# ttgo-diy.net
KiCad netlist of a schematic drawn in EAGLE
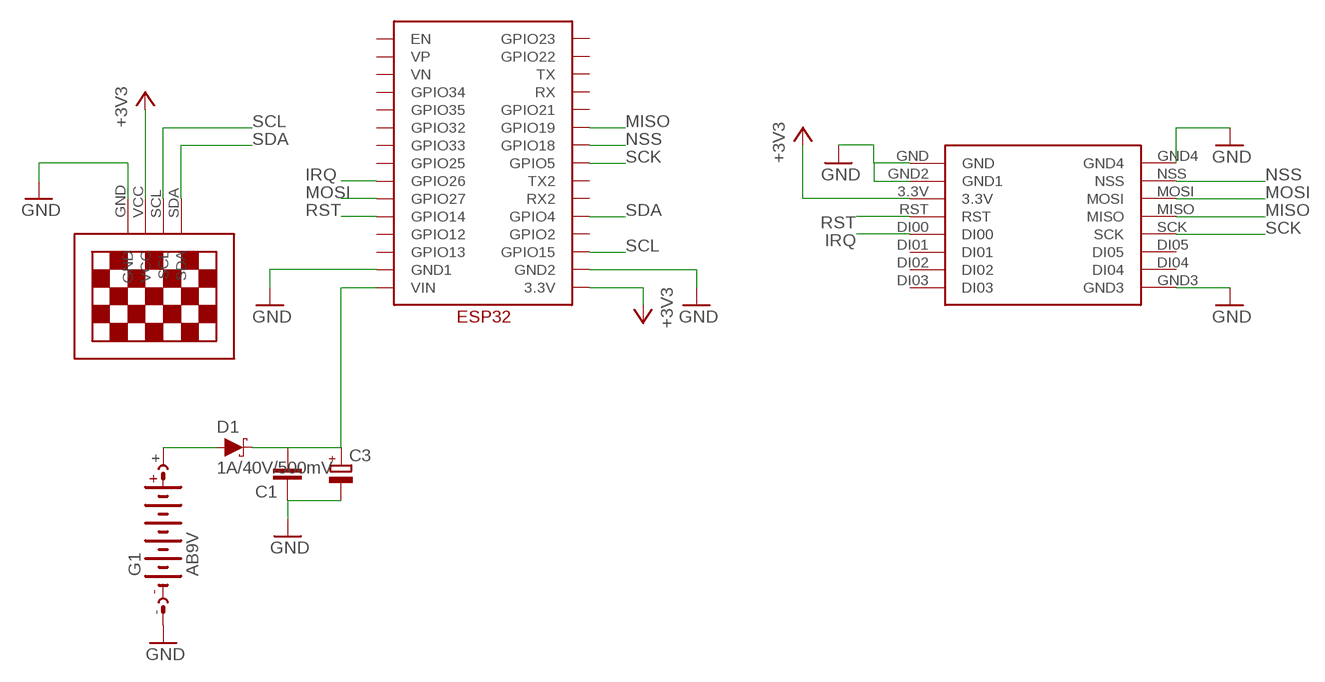
[diagram p0: schematic, sheet 1]

(export (version "E")
  (design (tool "Eeschema 10.0.6"))
  (components
    (comp (ref "C1")
      (value "C-EUC1206")
      (footprint "eagle-import:C1206")
      (libsource (lib "eagle-import") (part "C-EUC1206"))
    )
    (comp (ref "C3")
      (value "CPOL-EUCT6032")
      (footprint "eagle-import:CT6032")
      (libsource (lib "eagle-import") (part "CPOL-EUCT6032"))
    )
    (comp (ref "D1")
      (value "1A/40V/500mV")
      (footprint "eagle-import:SMA-DIODE")
      (libsource (lib "eagle-import") (part "DIODE-SCHOTTKY-SS14"))
    )
    (comp (ref "G1")
      (value "AB9V")
      (footprint "eagle-import:AB9V")
      (libsource (lib "eagle-import") (part "AB9V"))
    )
    (comp (ref "U$1")
      (value "LORA-02DIL")
      (footprint "eagle-import:DIL8X11")
      (libsource (lib "eagle-import") (part "LORA-02DIL"))
    )
    (comp (ref "U$2")
      (value "ESP32")
      (footprint "eagle-import:ESP32")
      (libsource (lib "eagle-import") (part "ESP32"))
    )
    (comp (ref "U$3")
      (value "13\"OLED13\"OLED")
      (footprint "eagle-import:1.3_OLED")
      (libsource (lib "eagle-import") (part "13{dblquote}OLED13{dblquote}OLED"))
    )
  )
  (nets
    (net (code "1") (name "+3V3") (class "Default")
      (node (ref "U$1") (pin "3.3V") (pinfunction "3.3V_3.3V") (pintype "power_in"))
      (node (ref "U$2") (pin "3.3V") (pinfunction "3.3V_3.3V") (pintype "bidirectional"))
      (node (ref "U$3") (pin "VCC") (pinfunction "VCC_VCC") (pintype "bidirectional"))
    )
    (net (code "2") (name "/IRQ") (class "Default")
      (node (ref "U$1") (pin "DI00") (pinfunction "DI00_DI00") (pintype "bidirectional"))
      (node (ref "U$2") (pin "GPIO26") (pinfunction "GPIO26_GPIO26") (pintype "bidirectional"))
    )
    (net (code "3") (name "/MISO") (class "Default")
      (node (ref "U$1") (pin "MISO") (pinfunction "MISO_MISO") (pintype "input"))
      (node (ref "U$2") (pin "GPIO19") (pinfunction "GPIO19_GPIO19") (pintype "bidirectional"))
    )
    (net (code "4") (name "/MOSI") (class "Default")
      (node (ref "U$1") (pin "MOSI") (pinfunction "MOSI_MOSI") (pintype "output"))
      (node (ref "U$2") (pin "GPIO27") (pinfunction "GPIO27_GPIO27") (pintype "bidirectional"))
    )
    (net (code "5") (name "/NSS") (class "Default")
      (node (ref "U$1") (pin "NSS") (pinfunction "NSS_NSS") (pintype "input"))
      (node (ref "U$2") (pin "GPIO18") (pinfunction "GPIO18_GPIO18") (pintype "bidirectional"))
    )
    (net (code "6") (name "/RST") (class "Default")
      (node (ref "U$1") (pin "RST") (pinfunction "RST_RST") (pintype "input"))
      (node (ref "U$2") (pin "GPIO14") (pinfunction "GPIO14_GPIO14") (pintype "bidirectional"))
    )
    (net (code "7") (name "/SCK") (class "Default")
      (node (ref "U$1") (pin "SCK") (pinfunction "SCK_SCK") (pintype "open_collector"))
      (node (ref "U$2") (pin "GPIO5") (pinfunction "GPIO5_GPIO5") (pintype "bidirectional"))
    )
    (net (code "8") (name "/SCL") (class "Default")
      (node (ref "U$2") (pin "GPIO15") (pinfunction "GPIO15_GPIO15") (pintype "bidirectional"))
      (node (ref "U$3") (pin "SCL") (pinfunction "SCL_SCL") (pintype "bidirectional"))
    )
    (net (code "9") (name "/SDA") (class "Default")
      (node (ref "U$2") (pin "GPIO4") (pinfunction "GPIO4_GPIO4") (pintype "bidirectional"))
      (node (ref "U$3") (pin "SDA") (pinfunction "SDA_SDA") (pintype "bidirectional"))
    )
    (net (code "10") (name "GND") (class "Default")
      (node (ref "C1") (pin "1") (pinfunction "1_1") (pintype "passive"))
      (node (ref "C3") (pin "-") (pinfunction "-_-") (pintype "passive"))
      (node (ref "G1") (pin "-") (pinfunction "-_-") (pintype "passive"))
      (node (ref "U$1") (pin "GND") (pinfunction "GND_GND") (pintype "power_in"))
      (node (ref "U$1") (pin "GND2") (pinfunction "GND1_GND2") (pintype "power_in"))
      (node (ref "U$1") (pin "GND3") (pinfunction "GND3_GND3") (pintype "power_in"))
      (node (ref "U$1") (pin "GND4") (pinfunction "GND4_GND4") (pintype "power_in"))
      (node (ref "U$2") (pin "GND1") (pinfunction "GND1_GND1") (pintype "bidirectional"))
      (node (ref "U$2") (pin "GND2") (pinfunction "GND2_GND2") (pintype "bidirectional"))
      (node (ref "U$3") (pin "GND") (pinfunction "GND_GND") (pintype "bidirectional"))
    )
    (net (code "11") (name "Net-(C1-Pad2)") (class "Default")
      (node (ref "C1") (pin "2") (pinfunction "2_2") (pintype "passive"))
      (node (ref "C3") (pin "+") (pinfunction "+_+") (pintype "passive"))
      (node (ref "D1") (pin "C") (pinfunction "C_C") (pintype "passive"))
      (node (ref "U$2") (pin "VIN") (pinfunction "VIN_VIN") (pintype "bidirectional"))
    )
    (net (code "12") (name "Net-(D1-PadA)") (class "Default")
      (node (ref "D1") (pin "A") (pinfunction "A_A") (pintype "passive"))
      (node (ref "G1") (pin "+") (pinfunction "+_+") (pintype "passive"))
    )
    (net (code "13") (name "unconnected-(U$1-PadDI01)") (class "Default")
      (node (ref "U$1") (pin "DI01") (pinfunction "DI01_DI01") (pintype "bidirectional"))
    )
    (net (code "14") (name "unconnected-(U$1-PadDI02)") (class "Default")
      (node (ref "U$1") (pin "DI02") (pinfunction "DI02_DI02") (pintype "bidirectional"))
    )
    (net (code "15") (name "unconnected-(U$1-PadDI03)") (class "Default")
      (node (ref "U$1") (pin "DI03") (pinfunction "DI03_DI03") (pintype "bidirectional"))
    )
    (net (code "16") (name "unconnected-(U$1-PadDI04)") (class "Default")
      (node (ref "U$1") (pin "DI04") (pinfunction "DI04_DI04") (pintype "bidirectional"))
    )
    (net (code "17") (name "unconnected-(U$1-PadDI05)") (class "Default")
      (node (ref "U$1") (pin "DI05") (pinfunction "DI05_DI05") (pintype "bidirectional"))
    )
    (net (code "18") (name "unconnected-(U$2-PadEN)") (class "Default")
      (node (ref "U$2") (pin "EN") (pinfunction "EN_EN") (pintype "bidirectional"))
    )
    (net (code "19") (name "unconnected-(U$2-PadGPIO2)") (class "Default")
      (node (ref "U$2") (pin "GPIO2") (pinfunction "GPIO2_GPIO2") (pintype "bidirectional"))
    )
    (net (code "20") (name "unconnected-(U$2-PadGPIO12)") (class "Default")
      (node (ref "U$2") (pin "GPIO12") (pinfunction "GPIO12_GPIO12") (pintype "bidirectional"))
    )
    (net (code "21") (name "unconnected-(U$2-PadGPIO13)") (class "Default")
      (node (ref "U$2") (pin "GPIO13") (pinfunction "GPIO13_GPIO13") (pintype "bidirectional"))
    )
    (net (code "22") (name "unconnected-(U$2-PadGPIO21)") (class "Default")
      (node (ref "U$2") (pin "GPIO21") (pinfunction "GPIO21_GPIO21") (pintype "bidirectional"))
    )
    (net (code "23") (name "unconnected-(U$2-PadGPIO22)") (class "Default")
      (node (ref "U$2") (pin "GPIO22") (pinfunction "GPIO22_GPIO22") (pintype "bidirectional"))
    )
    (net (code "24") (name "unconnected-(U$2-PadGPIO23)") (class "Default")
      (node (ref "U$2") (pin "GPIO23") (pinfunction "GPIO23_GPIO23") (pintype "bidirectional"))
    )
    (net (code "25") (name "unconnected-(U$2-PadGPIO25)") (class "Default")
      (node (ref "U$2") (pin "GPIO25") (pinfunction "GPIO25_GPIO25") (pintype "bidirectional"))
    )
    (net (code "26") (name "unconnected-(U$2-PadGPIO32)") (class "Default")
      (node (ref "U$2") (pin "GPIO32") (pinfunction "GPIO32_GPIO32") (pintype "bidirectional"))
    )
    (net (code "27") (name "unconnected-(U$2-PadGPIO33)") (class "Default")
      (node (ref "U$2") (pin "GPIO33") (pinfunction "GPIO33_GPIO33") (pintype "bidirectional"))
    )
    (net (code "28") (name "unconnected-(U$2-PadGPIO34)") (class "Default")
      (node (ref "U$2") (pin "GPIO34") (pinfunction "GPIO34_GPIO34") (pintype "bidirectional"))
    )
    (net (code "29") (name "unconnected-(U$2-PadGPIO35)") (class "Default")
      (node (ref "U$2") (pin "GPIO35") (pinfunction "GPIO35_GPIO35") (pintype "bidirectional"))
    )
    (net (code "30") (name "unconnected-(U$2-PadRX)") (class "Default")
      (node (ref "U$2") (pin "RX") (pinfunction "RX_RX") (pintype "bidirectional"))
    )
    (net (code "31") (name "unconnected-(U$2-PadRX2)") (class "Default")
      (node (ref "U$2") (pin "RX2") (pinfunction "RX2_RX2") (pintype "bidirectional"))
    )
    (net (code "32") (name "unconnected-(U$2-PadTX)") (class "Default")
      (node (ref "U$2") (pin "TX") (pinfunction "TX_TX") (pintype "bidirectional"))
    )
    (net (code "33") (name "unconnected-(U$2-PadTX2)") (class "Default")
      (node (ref "U$2") (pin "TX2") (pinfunction "TX2_TX2") (pintype "bidirectional"))
    )
    (net (code "34") (name "unconnected-(U$2-PadVN)") (class "Default")
      (node (ref "U$2") (pin "VN") (pinfunction "VN_VN") (pintype "bidirectional"))
    )
    (net (code "35") (name "unconnected-(U$2-PadVP)") (class "Default")
      (node (ref "U$2") (pin "VP") (pinfunction "VP_VP") (pintype "bidirectional"))
    )
  )
)
